# Level_Shifter_PCA9306JKZ.net
KiCad netlist of a schematic drawn in Altium Designer
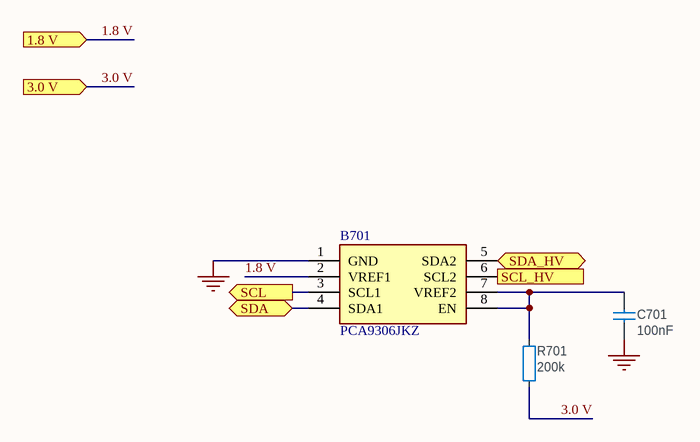
[diagram p0: Level Shifter (PCA9306JKZ).SchDoc]

(export (version "E")
  (design (tool "Eeschema 10.0.6"))
  (components
    (comp (ref "B701")
      (value "PCA9306JKZ")
      (footprint "PCA9306JKZ")
      (description "Dual Supply bidirectional I2C-bus and SMBus voltage-level translator")
      (fields (field (name "MANUFACTURER") "NXP Semiconductors"))
      (libsource (lib "Watch_Components") (part "PCA9306JKZ"))
    )
    (comp (ref "C701")
      (value "100nF")
      (footprint "CAPC0603X03L_C")
      (description "Capacitor, X7S, ±10%")
      (fields (field (name "AUTHOR") "rsk"))
      (libsource (lib "Watch_Components") (part "C0201-100n-16V-X7S"))
    )
    (comp (ref "R701")
      (value "200k")
      (footprint "RESC0603X03L_C")
      (description "Resistor, ±1%, 0.05W")
      (fields (field (name "AUTHOR") "rsk"))
      (libsource (lib "Watch_Components") (part "R0201"))
    )
  )
  (nets
    (net (code "1") (name "/1.8 V") (class "Default")
      (node (ref "B701") (pin "2") (pinfunction "VREF1_2") (pintype "passive"))
    )
    (net (code "2") (name "/3.0 V") (class "Default")
      (node (ref "R701") (pin "1") (pinfunction "1_1") (pintype "passive"))
    )
    (net (code "3") (name "/SCL") (class "Default")
      (node (ref "B701") (pin "3") (pinfunction "SCL1_3") (pintype "passive"))
    )
    (net (code "4") (name "/SCL_HV") (class "Default")
      (node (ref "B701") (pin "6") (pinfunction "SCL2_6") (pintype "passive"))
    )
    (net (code "5") (name "/SDA") (class "Default")
      (node (ref "B701") (pin "4") (pinfunction "SDA1_4") (pintype "passive"))
    )
    (net (code "6") (name "/SDA_HV") (class "Default")
      (node (ref "B701") (pin "5") (pinfunction "SDA2_5") (pintype "passive"))
    )
    (net (code "7") (name "GND") (class "Default")
      (node (ref "B701") (pin "1") (pinfunction "GND_1") (pintype "passive"))
      (node (ref "C701") (pin "1") (pinfunction "1_1") (pintype "passive"))
    )
    (net (code "8") (name "Net-(B701-EN)") (class "Default")
      (node (ref "B701") (pin "7") (pinfunction "VREF2_7") (pintype "passive"))
      (node (ref "B701") (pin "8") (pinfunction "EN_8") (pintype "passive"))
      (node (ref "C701") (pin "2") (pinfunction "2_2") (pintype "passive"))
      (node (ref "R701") (pin "2") (pinfunction "2_2") (pintype "passive"))
    )
  )
)
